# Week05_ElectronicsDesign_ADLL_FabAcademy.net
KiCad netlist of a schematic drawn in EAGLE
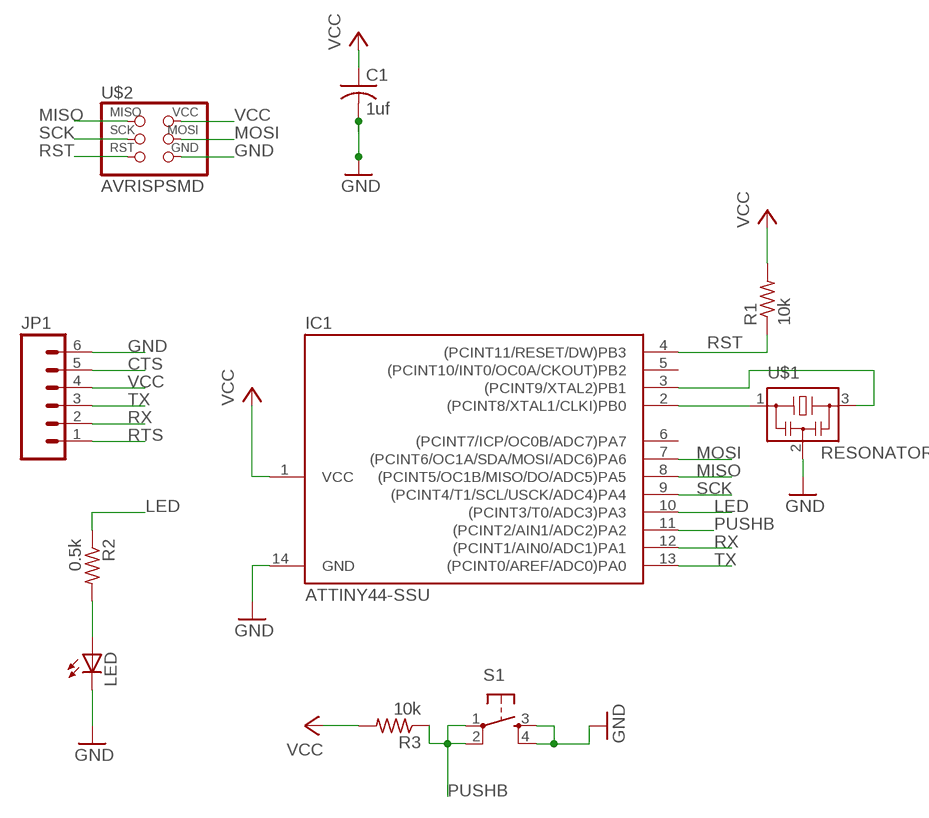
[diagram p0: schematic, sheet 1]

(export (version "E")
  (design (tool "Eeschema 10.0.6"))
  (components
    (comp (ref "C1")
      (value "1uf")
      (footprint "eagle-import:C1206")
      (libsource (lib "eagle-import") (part "C-USC1206"))
    )
    (comp (ref "IC1")
      (value "ATTINY44-SSU")
      (footprint "eagle-import:SOIC14")
      (libsource (lib "eagle-import") (part "ATTINY44-SSU"))
    )
    (comp (ref "JP1")
      (value "M06SMD")
      (footprint "eagle-import:1X06-SMD")
      (libsource (lib "eagle-import") (part "M06SMD"))
    )
    (comp (ref "LED")
      (value "LED1206")
      (footprint "eagle-import:1206")
      (libsource (lib "eagle-import") (part "LED1206"))
    )
    (comp (ref "R1")
      (value "10k")
      (footprint "eagle-import:R1206")
      (libsource (lib "eagle-import") (part "R-US_R1206"))
    )
    (comp (ref "R2")
      (value "0.5k")
      (footprint "eagle-import:R1206")
      (libsource (lib "eagle-import") (part "R-US_R1206"))
    )
    (comp (ref "R3")
      (value "10k")
      (footprint "eagle-import:R1206")
      (libsource (lib "eagle-import") (part "R-US_R1206"))
    )
    (comp (ref "S1")
      (value "6MM_SWITCH6MM_SWITCH")
      (footprint "eagle-import:6MM_SWITCH")
      (libsource (lib "eagle-import") (part "6MM_SWITCH6MM_SWITCH"))
    )
    (comp (ref "U$1")
      (value "RESONATOR")
      (footprint "eagle-import:EFOBM")
      (libsource (lib "eagle-import") (part "RESONATOR"))
    )
    (comp (ref "U$2")
      (value "AVRISPSMD")
      (footprint "eagle-import:2X03SMD")
      (libsource (lib "eagle-import") (part "AVRISPSMD"))
    )
  )
  (nets
    (net (code "1") (name "/CTS") (class "Default")
      (node (ref "JP1") (pin "5") (pinfunction "5_5") (pintype "passive"))
    )
    (net (code "2") (name "/LED") (class "Default")
      (node (ref "IC1") (pin "10") (pinfunction "(PCINT3/T0/ADC3)PA3_10") (pintype "bidirectional"))
      (node (ref "R2") (pin "1") (pinfunction "1_1") (pintype "passive"))
    )
    (net (code "3") (name "/MISO") (class "Default")
      (node (ref "IC1") (pin "8") (pinfunction "(PCINT5/OC1B/MISO/DO/ADC5)PA5_8") (pintype "bidirectional"))
      (node (ref "U$2") (pin "1") (pinfunction "MISO_1") (pintype "passive"))
    )
    (net (code "4") (name "/MOSI") (class "Default")
      (node (ref "IC1") (pin "7") (pinfunction "(PCINT6/OC1A/SDA/MOSI/ADC6)PA6_7") (pintype "bidirectional"))
      (node (ref "U$2") (pin "4") (pinfunction "MOSI_4") (pintype "passive"))
    )
    (net (code "5") (name "/PUSHB") (class "Default")
      (node (ref "IC1") (pin "11") (pinfunction "(PCINT2/AIN1/ADC2)PA2_11") (pintype "bidirectional"))
      (node (ref "R3") (pin "1") (pinfunction "1_1") (pintype "passive"))
      (node (ref "S1") (pin "1") (pinfunction "P_1") (pintype "passive"))
      (node (ref "S1") (pin "2") (pinfunction "P1_2") (pintype "passive"))
    )
    (net (code "6") (name "/RST") (class "Default")
      (node (ref "IC1") (pin "4") (pinfunction "(PCINT11/RESET/DW)PB3_4") (pintype "bidirectional"))
      (node (ref "R1") (pin "1") (pinfunction "1_1") (pintype "passive"))
      (node (ref "U$2") (pin "5") (pinfunction "RST_5") (pintype "passive"))
    )
    (net (code "7") (name "/RTS") (class "Default")
      (node (ref "JP1") (pin "1") (pinfunction "1_1") (pintype "passive"))
    )
    (net (code "8") (name "/RX") (class "Default")
      (node (ref "IC1") (pin "12") (pinfunction "(PCINT1/AIN0/ADC1)PA1_12") (pintype "bidirectional"))
      (node (ref "JP1") (pin "2") (pinfunction "2_2") (pintype "passive"))
    )
    (net (code "9") (name "/SCK") (class "Default")
      (node (ref "IC1") (pin "9") (pinfunction "(PCINT4/T1/SCL/USCK/ADC4)PA4_9") (pintype "bidirectional"))
      (node (ref "U$2") (pin "3") (pinfunction "SCK_3") (pintype "passive"))
    )
    (net (code "10") (name "/TX") (class "Default")
      (node (ref "IC1") (pin "13") (pinfunction "(PCINT0/AREF/ADC0)PA0_13") (pintype "bidirectional"))
      (node (ref "JP1") (pin "3") (pinfunction "3_3") (pintype "passive"))
    )
    (net (code "11") (name "GND") (class "Default")
      (node (ref "C1") (pin "2") (pinfunction "2_2") (pintype "passive"))
      (node (ref "IC1") (pin "14") (pinfunction "GND_14") (pintype "power_in"))
      (node (ref "JP1") (pin "6") (pinfunction "6_6") (pintype "passive"))
      (node (ref "LED") (pin "2") (pinfunction "C_2") (pintype "passive"))
      (node (ref "S1") (pin "3") (pinfunction "S_3") (pintype "passive"))
      (node (ref "S1") (pin "4") (pinfunction "S1_4") (pintype "passive"))
      (node (ref "U$1") (pin "2") (pinfunction "2_2") (pintype "passive"))
      (node (ref "U$2") (pin "6") (pinfunction "GND_6") (pintype "passive"))
    )
    (net (code "12") (name "Net-(IC1-(PCINT8{slash}XTAL1{slash}CLKI)PB0)") (class "Default")
      (node (ref "IC1") (pin "2") (pinfunction "(PCINT8/XTAL1/CLKI)PB0_2") (pintype "bidirectional"))
      (node (ref "U$1") (pin "1") (pinfunction "1_1") (pintype "passive"))
    )
    (net (code "13") (name "Net-(IC1-(PCINT9{slash}XTAL2)PB1)") (class "Default")
      (node (ref "IC1") (pin "3") (pinfunction "(PCINT9/XTAL2)PB1_3") (pintype "bidirectional"))
      (node (ref "U$1") (pin "3") (pinfunction "3_3") (pintype "passive"))
    )
    (net (code "14") (name "Net-(LED-A)") (class "Default")
      (node (ref "LED") (pin "1") (pinfunction "A_1") (pintype "passive"))
      (node (ref "R2") (pin "2") (pinfunction "2_2") (pintype "passive"))
    )
    (net (code "15") (name "VCC") (class "Default")
      (node (ref "C1") (pin "1") (pinfunction "1_1") (pintype "passive"))
      (node (ref "IC1") (pin "1") (pinfunction "VCC_1") (pintype "power_in"))
      (node (ref "JP1") (pin "4") (pinfunction "4_4") (pintype "passive"))
      (node (ref "R1") (pin "2") (pinfunction "2_2") (pintype "passive"))
      (node (ref "R3") (pin "2") (pinfunction "2_2") (pintype "passive"))
      (node (ref "U$2") (pin "2") (pinfunction "VCC_2") (pintype "passive"))
    )
    (net (code "16") (name "unconnected-(IC1-(PCINT7{slash}ICP{slash}OC0B{slash}ADC7)PA7-Pad6)") (class "Default")
      (node (ref "IC1") (pin "6") (pinfunction "(PCINT7/ICP/OC0B/ADC7)PA7_6") (pintype "bidirectional"))
    )
    (net (code "17") (name "unconnected-(IC1-(PCINT10{slash}INT0{slash}OC0A{slash}CKOUT)PB2-Pad5)") (class "Default")
      (node (ref "IC1") (pin "5") (pinfunction "(PCINT10/INT0/OC0A/CKOUT)PB2_5") (pintype "bidirectional"))
    )
  )
)
